# SB_MAIN.net
KiCad netlist of a schematic drawn in Altium Designer
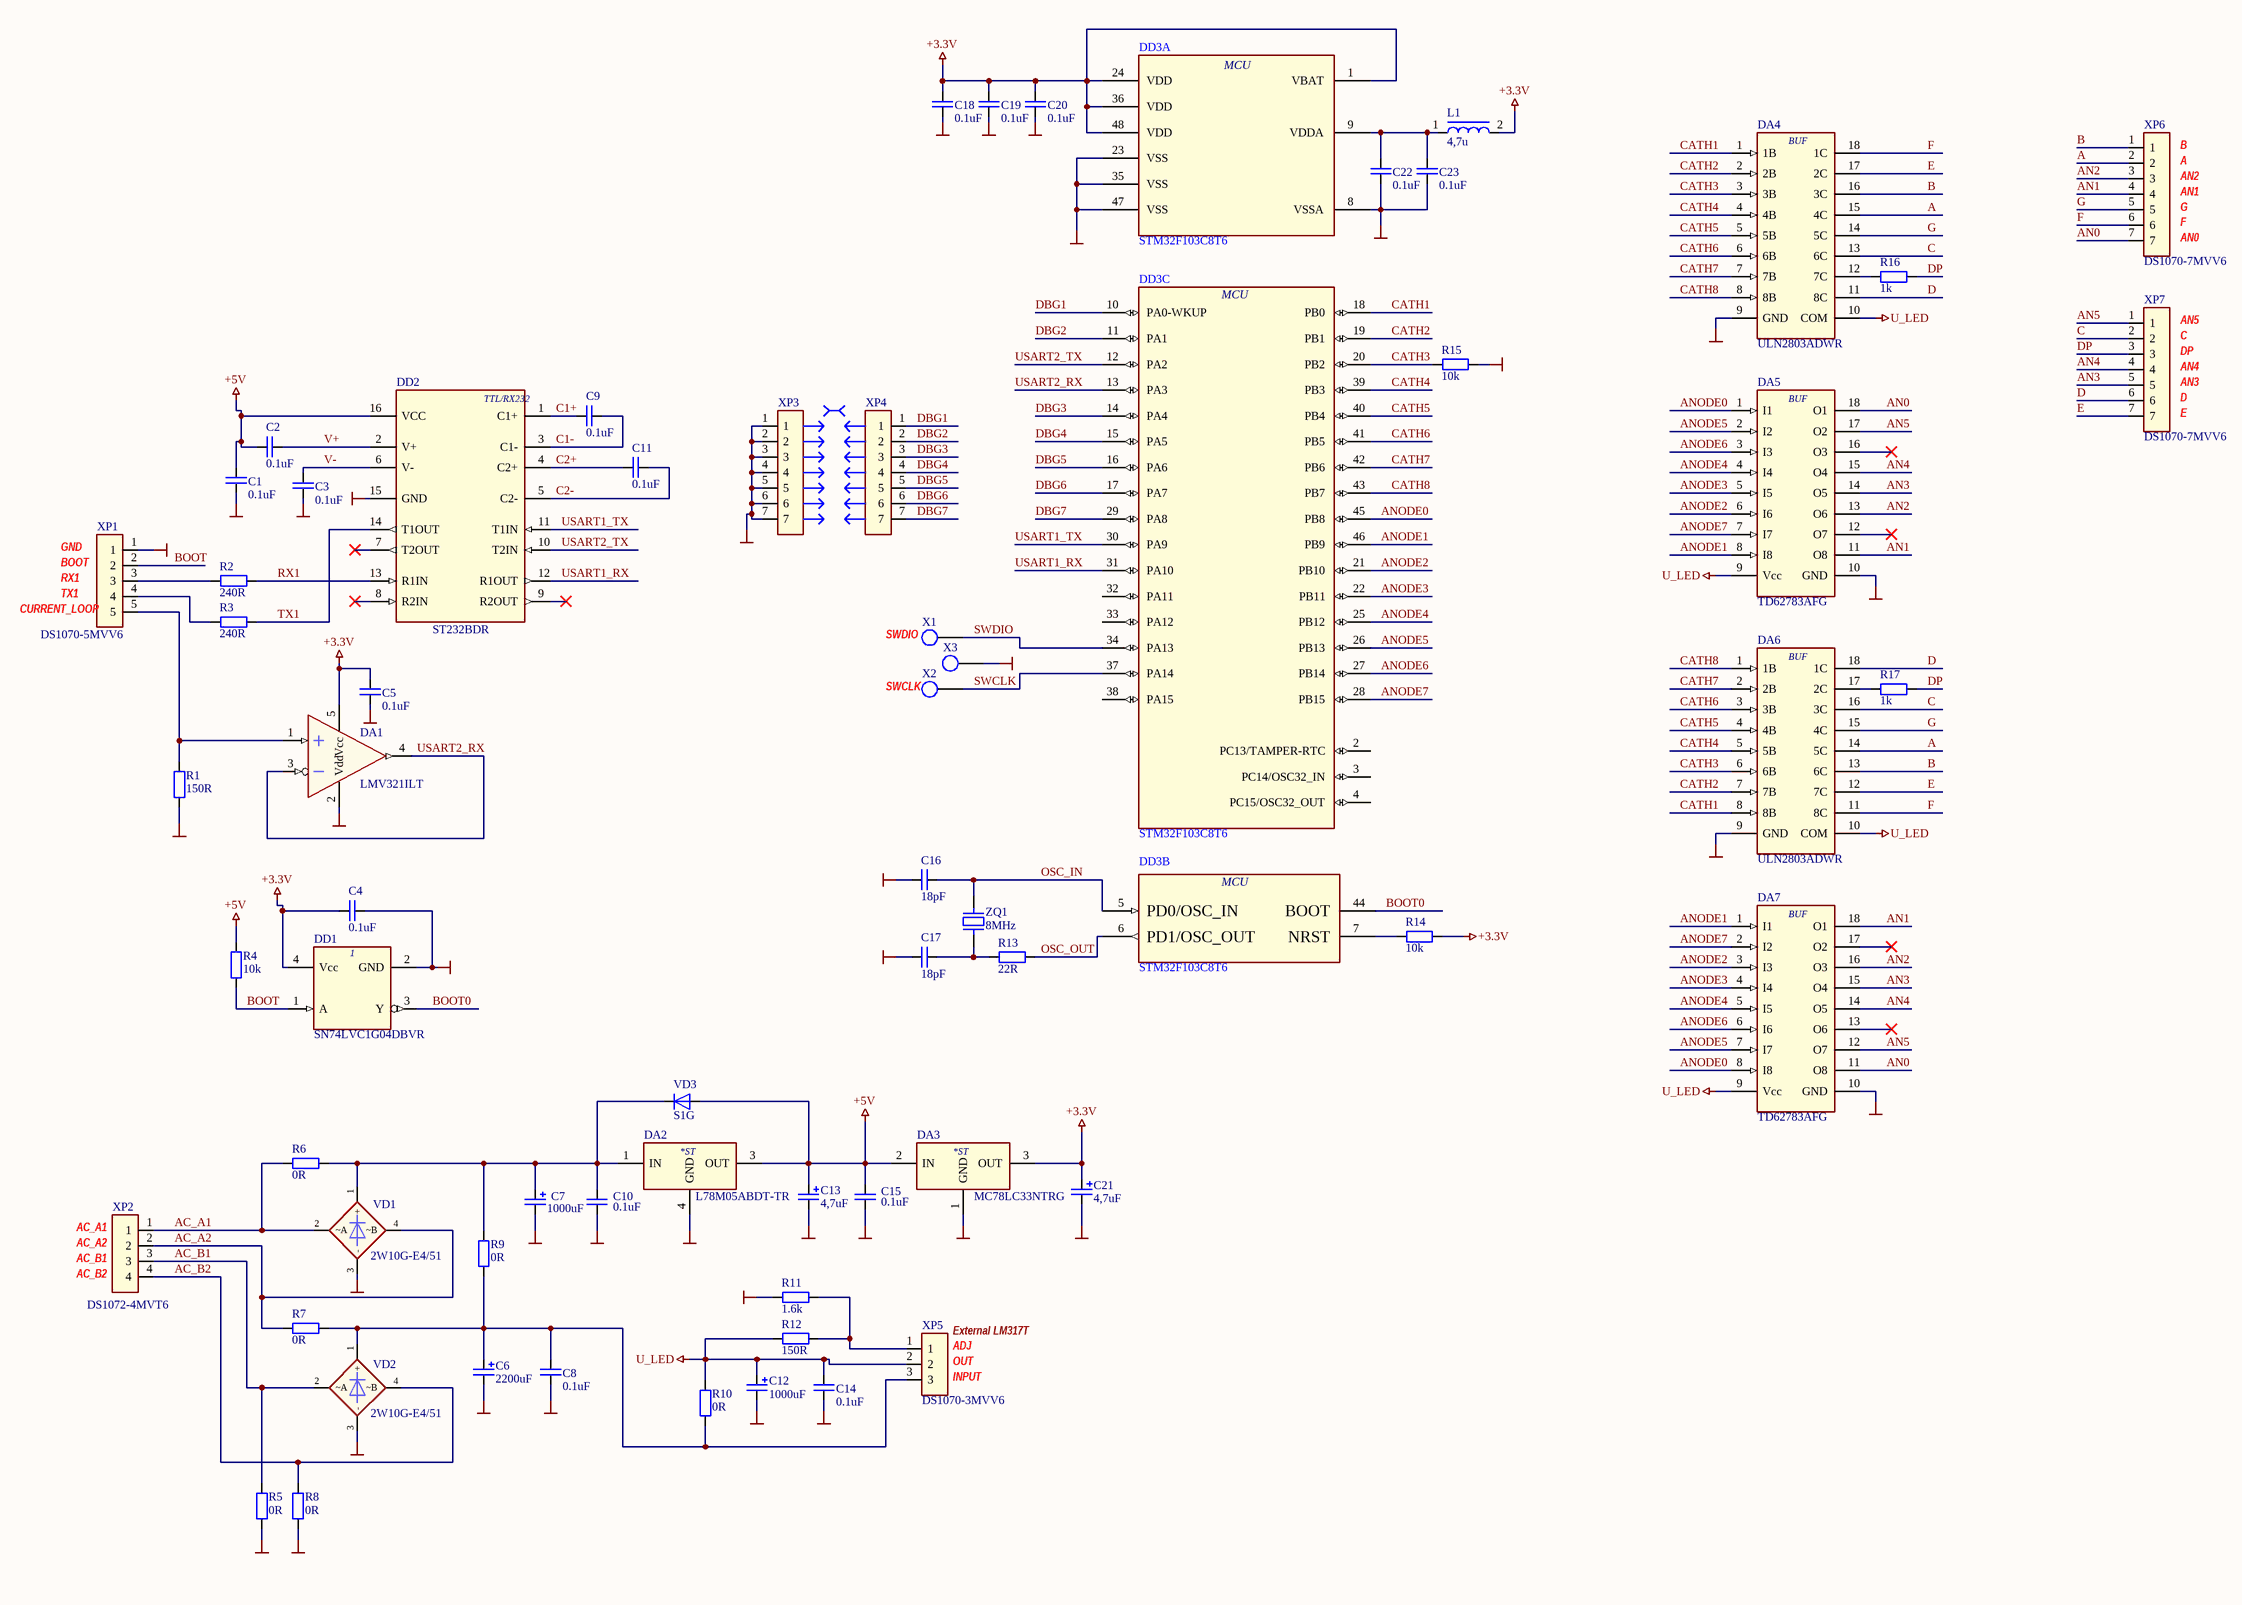
[diagram p0: SB_MAIN.SchDoc]

(export (version "E")
  (design (tool "Eeschema 10.0.6"))
  (components
    (comp (ref "C1")
      (value "0.1uF")
      (footprint "CAPC2012X14N")
      (description "Конденсатор 0805-X7R-50В-0,1мкФ ± 10%")
      (fields
        (field (name "MANUFACTURER PART NUMBER") "GRM21BR71H104KA01L")
        (field (name "MANUFACTURER") "Murata Electronics")
      )
      (libsource (lib "configDatabaseAD") (part "CapacitorsUnpolarized"))
    )
    (comp (ref "C2")
      (value "0.1uF")
      (footprint "CAPC2012X14N")
      (description "Конденсатор 0805-X7R-50В-0,1мкФ ± 10%")
      (fields
        (field (name "MANUFACTURER PART NUMBER") "GRM21BR71H104KA01L")
        (field (name "MANUFACTURER") "Murata Electronics")
      )
      (libsource (lib "configDatabaseAD") (part "CapacitorsUnpolarized"))
    )
    (comp (ref "C3")
      (value "0.1uF")
      (footprint "CAPC2012X14N")
      (description "Конденсатор 0805-X7R-50В-0,1мкФ ± 10%")
      (fields
        (field (name "MANUFACTURER PART NUMBER") "GRM21BR71H104KA01L")
        (field (name "MANUFACTURER") "Murata Electronics")
      )
      (libsource (lib "configDatabaseAD") (part "CapacitorsUnpolarized"))
    )
    (comp (ref "C4")
      (value "0.1uF")
      (footprint "CAPC2012X14N")
      (description "Конденсатор 0805-X7R-50В-0,1мкФ ± 10%")
      (fields
        (field (name "MANUFACTURER PART NUMBER") "GRM21BR71H104KA01L")
        (field (name "MANUFACTURER") "Murata Electronics")
      )
      (libsource (lib "configDatabaseAD") (part "CapacitorsUnpolarized"))
    )
    (comp (ref "C5")
      (value "0.1uF")
      (footprint "CAPC2012X14N")
      (description "Конденсатор 0805-X7R-50В-0,1мкФ ± 10%")
      (fields
        (field (name "MANUFACTURER PART NUMBER") "GRM21BR71H104KA01L")
        (field (name "MANUFACTURER") "Murata Electronics")
      )
      (libsource (lib "configDatabaseAD") (part "CapacitorsUnpolarized"))
    )
    (comp (ref "C6")
      (value "2200uF")
      (footprint "CAPR16X25")
      (description "Конденсатор электролитический 35В-2200мкФ ± 20%")
      (fields
        (field (name "MANUFACTURER PART NUMBER") "TKR222M1VK25")
        (field (name "MANUFACTURER") "Jamicon")
      )
      (libsource (lib "configDatabaseAD") (part "CapacitorsPolarized"))
    )
    (comp (ref "C7")
      (value "1000uF")
      (footprint "CAPR10x21")
      (description "Конденсатор электролитический 25В-1000мкФ ± 20%")
      (fields
        (field (name "MANUFACTURER PART NUMBER") "WLR102M1EG21")
        (field (name "MANUFACTURER") "Jamicon")
      )
      (libsource (lib "configDatabaseAD") (part "CapacitorsPolarized"))
    )
    (comp (ref "C8")
      (value "0.1uF")
      (footprint "JFA11x13x7.5")
      (description "Конденсатор-100В-0,1мкФ ± 5%")
      (fields
        (field (name "MANUFACTURER PART NUMBER") "JFA02A104J075000B")
        (field (name "MANUFACTURER") "JB")
      )
      (libsource (lib "configDatabaseAD") (part "CapacitorsUnpolarized"))
    )
    (comp (ref "C9")
      (value "0.1uF")
      (footprint "CAPC2012X14N")
      (description "Конденсатор 0805-X7R-50В-0,1мкФ ± 10%")
      (fields
        (field (name "MANUFACTURER PART NUMBER") "GRM21BR71H104KA01L")
        (field (name "MANUFACTURER") "Murata Electronics")
      )
      (libsource (lib "configDatabaseAD") (part "CapacitorsUnpolarized"))
    )
    (comp (ref "C10")
      (value "0.1uF")
      (footprint "JFA11x13x7.5")
      (description "Конденсатор-100В-0,1мкФ ± 5%")
      (fields
        (field (name "MANUFACTURER PART NUMBER") "JFA02A104J075000B")
        (field (name "MANUFACTURER") "JB")
      )
      (libsource (lib "configDatabaseAD") (part "CapacitorsUnpolarized"))
    )
    (comp (ref "C11")
      (value "0.1uF")
      (footprint "CAPC2012X14N")
      (description "Конденсатор 0805-X7R-50В-0,1мкФ ± 10%")
      (fields
        (field (name "MANUFACTURER PART NUMBER") "GRM21BR71H104KA01L")
        (field (name "MANUFACTURER") "Murata Electronics")
      )
      (libsource (lib "configDatabaseAD") (part "CapacitorsUnpolarized"))
    )
    (comp (ref "C12")
      (value "1000uF")
      (footprint "CAPR10x21")
      (description "Конденсатор электролитический 25В-1000мкФ ± 20%")
      (fields
        (field (name "MANUFACTURER PART NUMBER") "WLR102M1EG21")
        (field (name "MANUFACTURER") "Jamicon")
      )
      (libsource (lib "configDatabaseAD") (part "CapacitorsPolarized"))
    )
    (comp (ref "C13")
      (value "4,7uF")
      (footprint "CAPMP3217X18N")
      (description "Конденсатор танталовый 10В-4,7мкФ ± 10%")
      (fields
        (field (name "MANUFACTURER PART NUMBER") "TECAP4,7/10VA10")
        (field (name "MANUFACTURER") "NoName")
      )
      (libsource (lib "configDatabaseAD") (part "CapacitorsPolarized"))
    )
    (comp (ref "C14")
      (value "0.1uF")
      (footprint "JFA11x13x7.5")
      (description "Конденсатор-100В-0,1мкФ ± 5%")
      (fields
        (field (name "MANUFACTURER PART NUMBER") "JFA02A104J075000B")
        (field (name "MANUFACTURER") "JB")
      )
      (libsource (lib "configDatabaseAD") (part "CapacitorsUnpolarized"))
    )
    (comp (ref "C15")
      (value "0.1uF")
      (footprint "JFA11x13x7.5")
      (description "Конденсатор-100В-0,1мкФ ± 5%")
      (fields
        (field (name "MANUFACTURER PART NUMBER") "JFA02A104J075000B")
        (field (name "MANUFACTURER") "JB")
      )
      (libsource (lib "configDatabaseAD") (part "CapacitorsUnpolarized"))
    )
    (comp (ref "C16")
      (value "18pF")
      (footprint "CAPC2012X14N")
      (description "Конденсатор 0805-C0G-50В-18пФ ± 5%")
      (fields
        (field (name "MANUFACTURER PART NUMBER") "GRM2165C1H180JD01D")
        (field (name "MANUFACTURER") "Murata Electronics")
      )
      (libsource (lib "configDatabaseAD") (part "CapacitorsUnpolarized"))
    )
    (comp (ref "C17")
      (value "18pF")
      (footprint "CAPC2012X14N")
      (description "Конденсатор 0805-C0G-50В-18пФ ± 5%")
      (fields
        (field (name "MANUFACTURER PART NUMBER") "GRM2165C1H180JD01D")
        (field (name "MANUFACTURER") "Murata Electronics")
      )
      (libsource (lib "configDatabaseAD") (part "CapacitorsUnpolarized"))
    )
    (comp (ref "C18")
      (value "0.1uF")
      (footprint "CAPC2012X14N")
      (description "Конденсатор 0805-X7R-50В-0,1мкФ ± 10%")
      (fields
        (field (name "MANUFACTURER PART NUMBER") "GRM21BR71H104KA01L")
        (field (name "MANUFACTURER") "Murata Electronics")
      )
      (libsource (lib "configDatabaseAD") (part "CapacitorsUnpolarized"))
    )
    (comp (ref "C19")
      (value "0.1uF")
      (footprint "CAPC2012X14N")
      (description "Конденсатор 0805-X7R-50В-0,1мкФ ± 10%")
      (fields
        (field (name "MANUFACTURER PART NUMBER") "GRM21BR71H104KA01L")
        (field (name "MANUFACTURER") "Murata Electronics")
      )
      (libsource (lib "configDatabaseAD") (part "CapacitorsUnpolarized"))
    )
    (comp (ref "C20")
      (value "0.1uF")
      (footprint "CAPC2012X14N")
      (description "Конденсатор 0805-X7R-50В-0,1мкФ ± 10%")
      (fields
        (field (name "MANUFACTURER PART NUMBER") "GRM21BR71H104KA01L")
        (field (name "MANUFACTURER") "Murata Electronics")
      )
      (libsource (lib "configDatabaseAD") (part "CapacitorsUnpolarized"))
    )
    (comp (ref "C21")
      (value "4,7uF")
      (footprint "CAPMP3217X18N")
      (description "Конденсатор танталовый 10В-4,7мкФ ± 10%")
      (fields
        (field (name "MANUFACTURER PART NUMBER") "TECAP4,7/10VA10")
        (field (name "MANUFACTURER") "NoName")
      )
      (libsource (lib "configDatabaseAD") (part "CapacitorsPolarized"))
    )
    (comp (ref "C22")
      (value "0.1uF")
      (footprint "CAPC2012X14N")
      (description "Конденсатор 0805-X7R-50В-0,1мкФ ± 10%")
      (fields
        (field (name "MANUFACTURER PART NUMBER") "GRM21BR71H104KA01L")
        (field (name "MANUFACTURER") "Murata Electronics")
      )
      (libsource (lib "configDatabaseAD") (part "CapacitorsUnpolarized"))
    )
    (comp (ref "C23")
      (value "0.1uF")
      (footprint "CAPC2012X14N")
      (description "Конденсатор 0805-X7R-50В-0,1мкФ ± 10%")
      (fields
        (field (name "MANUFACTURER PART NUMBER") "GRM21BR71H104KA01L")
        (field (name "MANUFACTURER") "Murata Electronics")
      )
      (libsource (lib "configDatabaseAD") (part "CapacitorsUnpolarized"))
    )
    (comp (ref "DA1")
      (value "LMV321ILT")
      (footprint "SOT95P280X145-5N")
      (description "Микросхема LMV321ILT")
      (fields (field (name "MANUFACTURER") "STMicroelectronics"))
      (libsource (lib "configDatabaseAD") (part "LMV321ILT"))
    )
    (comp (ref "DA2")
      (value "L78M05ABDT-TR")
      (footprint "DPAK228P1010X238-3N")
      (description "Микросхема L78M05ABDT-TR")
      (fields (field (name "MANUFACTURER") "STMicroelectronics"))
      (libsource (lib "configDatabaseAD") (part "L78MxxxxDT-TR"))
    )
    (comp (ref "DA3")
      (value "MC78LC33NTRG")
      (footprint "SOT89-150P350X160-3M")
      (description "Микросхема MC78LC33NTRG")
      (fields (field (name "MANUFACTURER") "ON Semiconductor"))
      (libsource (lib "configDatabaseAD") (part "MC78LCxxNTRG"))
    )
    (comp (ref "DA4")
      (value "ULN2803ADWR")
      (footprint "SOIC127P1030X265-18N")
      (description "Микросхема ULN2803ADWR")
      (fields (field (name "MANUFACTURER") "Texas Instruments"))
      (libsource (lib "configDatabaseAD") (part "ULN2803A"))
    )
    (comp (ref "DA5")
      (value "TD62783AFG")
      (footprint "SOIC127P1020X245-18N")
      (description "Микросхема TD62783AFG")
      (fields (field (name "MANUFACTURER") "Toshiba"))
      (libsource (lib "configDatabaseAD") (part "TD62783"))
    )
    (comp (ref "DA6")
      (value "ULN2803ADWR")
      (footprint "SOIC127P1030X265-18N")
      (description "Микросхема ULN2803ADWR")
      (fields (field (name "MANUFACTURER") "Texas Instruments"))
      (libsource (lib "configDatabaseAD") (part "ULN2803A"))
    )
    (comp (ref "DA7")
      (value "TD62783AFG")
      (footprint "SOIC127P1020X245-18N")
      (description "Микросхема TD62783AFG")
      (fields (field (name "MANUFACTURER") "Toshiba"))
      (libsource (lib "configDatabaseAD") (part "TD62783"))
    )
    (comp (ref "DD1")
      (value "SN74LVC1G04DBVR")
      (footprint "SOT95P280X145-5N")
      (description "Микросхема SN74LVC1G04DBVR")
      (fields (field (name "MANUFACTURER") "Texas Instruments"))
      (libsource (lib "configDatabaseAD") (part "SN74LVC1G04"))
    )
    (comp (ref "DD2")
      (value "ST232BDR")
      (footprint "SOIC127P600X175-16N")
      (description "Микросхема ST232BDR")
      (fields (field (name "MANUFACTURER") "STMicroelectronics"))
      (libsource (lib "configDatabaseAD") (part "ST232"))
    )
    (comp (ref "DD3")
      (value "STM32F103C8T6")
      (footprint "TSQFP50P900X900X160-48M")
      (description "Микросхема STM32F103C8T6")
      (fields (field (name "MANUFACTURER") "STMicroelectronics"))
      (libsource (lib "configDatabaseAD") (part "STM32F103Cxxx"))
    )
    (comp (ref "L1")
      (value "4,7u")
      (footprint "INDC2012X10N")
      (description "Индуктивность 0805-4,7мкГ ± 30%")
      (fields
        (field (name "MANUFACTURER PART NUMBER") "LQM21PN4R7NGR")
        (field (name "MANUFACTURER") "Murata Electronics")
      )
      (libsource (lib "configDatabaseAD") (part "Inductor"))
    )
    (comp (ref "R1")
      (value "150R")
      (footprint "RESC2012X06N")
      (description "Резистор 0805-0,125Вт-150Ом ± 1%")
      (fields
        (field (name "MANUFACTURER PART NUMBER") "RC0805FR-07150RL")
        (field (name "MANUFACTURER") "Yageo")
      )
      (libsource (lib "configDatabaseAD") (part "Resistor"))
    )
    (comp (ref "R2")
      (value "240R")
      (footprint "RESC2012X06N")
      (description "Резистор 0805-0,125Вт-240Ом ± 1%")
      (fields
        (field (name "MANUFACTURER PART NUMBER") "RC0805FR-07240RL")
        (field (name "MANUFACTURER") "Yageo")
      )
      (libsource (lib "configDatabaseAD") (part "Resistor"))
    )
    (comp (ref "R3")
      (value "240R")
      (footprint "RESC2012X06N")
      (description "Резистор 0805-0,125Вт-240Ом ± 1%")
      (fields
        (field (name "MANUFACTURER PART NUMBER") "RC0805FR-07240RL")
        (field (name "MANUFACTURER") "Yageo")
      )
      (libsource (lib "configDatabaseAD") (part "Resistor"))
    )
    (comp (ref "R4")
      (value "10k")
      (footprint "RESC2012X06N")
      (description "Резистор 0805-0,125Вт-10кОм ± 1%")
      (fields
        (field (name "MANUFACTURER PART NUMBER") "RC0805FR-0710KL")
        (field (name "MANUFACTURER") "Yageo")
      )
      (libsource (lib "configDatabaseAD") (part "Resistor"))
    )
    (comp (ref "R5")
      (value "0R")
      (footprint "RESC6332X06N")
      (description "Резистор 2512-1Вт-0Ом ± 1%")
      (fields
        (field (name "MANUFACTURER PART NUMBER") "RC2512FR-070RL")
        (field (name "MANUFACTURER") "Yageo")
      )
      (libsource (lib "configDatabaseAD") (part "Resistor"))
    )
    (comp (ref "R6")
      (value "0R")
      (footprint "RESC6332X06N")
      (description "Резистор 2512-1Вт-0Ом ± 1%")
      (fields
        (field (name "MANUFACTURER PART NUMBER") "RC2512FR-070RL")
        (field (name "MANUFACTURER") "Yageo")
      )
      (libsource (lib "configDatabaseAD") (part "Resistor"))
    )
    (comp (ref "R7")
      (value "0R")
      (footprint "RESC6332X06N")
      (description "Резистор 2512-1Вт-0Ом ± 1%")
      (fields
        (field (name "MANUFACTURER PART NUMBER") "RC2512FR-070RL")
        (field (name "MANUFACTURER") "Yageo")
      )
      (libsource (lib "configDatabaseAD") (part "Resistor"))
    )
    (comp (ref "R8")
      (value "0R")
      (footprint "RESC6332X06N")
      (description "Резистор 2512-1Вт-0Ом ± 1%")
      (fields
        (field (name "MANUFACTURER PART NUMBER") "RC2512FR-070RL")
        (field (name "MANUFACTURER") "Yageo")
      )
      (libsource (lib "configDatabaseAD") (part "Resistor"))
    )
    (comp (ref "R9")
      (value "0R")
      (footprint "RESC6332X06N")
      (description "Резистор 2512-1Вт-0Ом ± 1%")
      (fields
        (field (name "MANUFACTURER PART NUMBER") "RC2512FR-070RL")
        (field (name "MANUFACTURER") "Yageo")
      )
      (libsource (lib "configDatabaseAD") (part "Resistor"))
    )
    (comp (ref "R10")
      (value "0R")
      (footprint "RESC6332X06N")
      (description "Резистор 2512-1Вт-0Ом ± 1%")
      (fields
        (field (name "MANUFACTURER PART NUMBER") "RC2512FR-070RL")
        (field (name "MANUFACTURER") "Yageo")
      )
      (libsource (lib "configDatabaseAD") (part "Resistor"))
    )
    (comp (ref "R11")
      (value "1.6k")
      (footprint "RESC2012X06N")
      (description "Резистор 0805-0,125Вт-1,6кОм ± 1%")
      (fields
        (field (name "MANUFACTURER PART NUMBER") "RC0805FR-071K6L")
        (field (name "MANUFACTURER") "Yageo")
      )
      (libsource (lib "configDatabaseAD") (part "Resistor"))
    )
    (comp (ref "R12")
      (value "150R")
      (footprint "RESC2012X06N")
      (description "Резистор 0805-0,125Вт-150Ом ± 1%")
      (fields
        (field (name "MANUFACTURER PART NUMBER") "RC0805FR-07150RL")
        (field (name "MANUFACTURER") "Yageo")
      )
      (libsource (lib "configDatabaseAD") (part "Resistor"))
    )
    (comp (ref "R13")
      (value "22R")
      (footprint "RESC2012X06N")
      (description "Резистор 0805-0,125Вт-22Ом ± 5%")
      (fields
        (field (name "MANUFACTURER PART NUMBER") "RC0805JR-0722RL")
        (field (name "MANUFACTURER") "Yageo")
      )
      (libsource (lib "configDatabaseAD") (part "Resistor"))
    )
    (comp (ref "R14")
      (value "10k")
      (footprint "RESC2012X06N")
      (description "Резистор 0805-0,125Вт-10кОм ± 1%")
      (fields
        (field (name "MANUFACTURER PART NUMBER") "RC0805FR-0710KL")
        (field (name "MANUFACTURER") "Yageo")
      )
      (libsource (lib "configDatabaseAD") (part "Resistor"))
    )
    (comp (ref "R15")
      (value "10k")
      (footprint "RESC2012X06N")
      (description "Резистор 0805-0,125Вт-10кОм ± 1%")
      (fields
        (field (name "MANUFACTURER PART NUMBER") "RC0805FR-0710KL")
        (field (name "MANUFACTURER") "Yageo")
      )
      (libsource (lib "configDatabaseAD") (part "Resistor"))
    )
    (comp (ref "R16")
      (value "1k")
      (footprint "RESC2012X06N")
      (description "Резистор 1206-0,25Вт-1кОм ± 1%")
      (fields
        (field (name "MANUFACTURER PART NUMBER") "RC1206FR-071KL")
        (field (name "MANUFACTURER") "Yageo")
      )
      (libsource (lib "configDatabaseAD") (part "Resistor"))
    )
    (comp (ref "R17")
      (value "1k")
      (footprint "RESC2012X06N")
      (description "Резистор 1206-0,25Вт-1кОм ± 1%")
      (fields
        (field (name "MANUFACTURER PART NUMBER") "RC1206FR-071KL")
        (field (name "MANUFACTURER") "Yageo")
      )
      (libsource (lib "configDatabaseAD") (part "Resistor"))
    )
    (comp (ref "VD1")
      (value "2W10G-E4/51")
      (footprint "DIOB_2W10")
      (description "Диод 2W10G-E4/51")
      (fields (field (name "MANUFACTURER") "Vishay"))
      (libsource (lib "configDatabaseAD") (part "Diod_Bridge"))
    )
    (comp (ref "VD2")
      (value "2W10G-E4/51")
      (footprint "DIOB_2W10")
      (description "Диод 2W10G-E4/51")
      (fields (field (name "MANUFACTURER") "Vishay"))
      (libsource (lib "configDatabaseAD") (part "Diod_Bridge"))
    )
    (comp (ref "VD3")
      (value "S1G")
      (footprint "DIOM4427X22M")
      (description "Диод S1G")
      (fields (field (name "MANUFACTURER") "Diotec Semiconductor"))
      (libsource (lib "configDatabaseAD") (part "Diod"))
    )
    (comp (ref "X1")
      (value "0,9mm")
      (footprint "PAD_HOLE_0.9MM")
      (fields
        (field (name "MANUFACTURER PART NUMBER") "PAD_1.8_HOLE_0.9MM")
        (field (name "MANUFACTURER") "NO BOM")
      )
      (libsource (lib "configDatabaseAD") (part "PAD_1_PIN"))
    )
    (comp (ref "X2")
      (value "0,9mm")
      (footprint "PAD_HOLE_0.9MM")
      (fields
        (field (name "MANUFACTURER PART NUMBER") "PAD_1.8_HOLE_0.9MM")
        (field (name "MANUFACTURER") "NO BOM")
      )
      (libsource (lib "configDatabaseAD") (part "PAD_1_PIN"))
    )
    (comp (ref "X3")
      (value "0,9mm")
      (footprint "PAD_HOLE_0.9MM")
      (fields
        (field (name "MANUFACTURER PART NUMBER") "PAD_1.8_HOLE_0.9MM")
        (field (name "MANUFACTURER") "NO BOM")
      )
      (libsource (lib "configDatabaseAD") (part "PAD_1_PIN"))
    )
    (comp (ref "XP1")
      (value "DS1070-5MVV6")
      (footprint "CONNFLY_DS1070-5MVV6")
      (description "Соединитель DS1070-5MVV6")
      (fields (field (name "MANUFACTURER") "Connfly"))
      (libsource (lib "configDatabaseAD") (part "Connector XP 5x1"))
    )
    (comp (ref "XP2")
      (value "DS1072-4MVT6")
      (footprint "CONNFLY_DS1072-4MVT6")
      (description "Соединитель DS1072-4MVT6")
      (fields (field (name "MANUFACTURER") "Connfly"))
      (libsource (lib "configDatabaseAD") (part "Connector XP 4x1"))
    )
    (comp (ref "XP3")
      (value "L-KLS1-207-1-07-S")
      (footprint "KLS_KLS1-207-1-07-S")
      (description "Соединитель DS1072-4MVT6")
      (fields (field (name "MANUFACTURER") "KLS"))
      (libsource (lib "configDatabaseAD") (part "Connector XP 7x1"))
    )
    (comp (ref "XP4")
      (value "L-KLS1-207-1-07-S")
      (footprint "KLS_KLS1-207-1-07-S")
      (description "Соединитель DS1072-4MVT6")
      (fields (field (name "MANUFACTURER") "KLS"))
      (libsource (lib "") (part "Connector XP 7x1_1"))
    )
    (comp (ref "XP5")
      (value "DS1070-3MVV6")
      (footprint "CONNFLY_DS1070-3MVV6")
      (description "Соединитель DS1070-3MVV6")
      (fields (field (name "MANUFACTURER") "Connfly"))
      (libsource (lib "configDatabaseAD") (part "Connector XP 3x1"))
    )
    (comp (ref "XP6")
      (value "DS1070-7MVV6")
      (footprint "CONNFLY_DS1070-7MVV6")
      (description "Соединитель DS1070-7MVV6")
      (fields (field (name "MANUFACTURER") "Connfly"))
      (libsource (lib "configDatabaseAD") (part "Connector XP 7x1"))
    )
    (comp (ref "XP7")
      (value "DS1070-7MVV6")
      (footprint "CONNFLY_DS1070-7MVV6")
      (description "Соединитель DS1070-7MVV6")
      (fields (field (name "MANUFACTURER") "Connfly"))
      (libsource (lib "configDatabaseAD") (part "Connector XP 7x1"))
    )
    (comp (ref "ZQ1")
      (value "8MHz")
      (footprint "KX-3H_spacer")
      (description "Кварцевый резонатор HC-49US-8MHz-16pF-30ppm")
      (fields
        (field (name "MANUFACTURER PART NUMBER") "HC-49US-8MHz-16pF-30ppm")
        (field (name "MANUFACTURER") "NoName")
      )
      (libsource (lib "configDatabaseAD") (part "QuartzCrystal"))
    )
  )
  (nets
    (net (code "1") (name "+3.3V") (class "Default")
      (node (ref "C18") (pin "2") (pinfunction "2_2") (pintype "passive"))
      (node (ref "C19") (pin "2") (pinfunction "2_2") (pintype "passive"))
      (node (ref "C20") (pin "2") (pinfunction "2_2") (pintype "passive"))
      (node (ref "C21") (pin "1") (pinfunction "P_1") (pintype "passive"))
      (node (ref "C4") (pin "1") (pinfunction "1_1") (pintype "passive"))
      (node (ref "C5") (pin "2") (pinfunction "2_2") (pintype "passive"))
      (node (ref "DA1") (pin "5") (pinfunction "Vcc_5") (pintype "power_in"))
      (node (ref "DA3") (pin "3") (pinfunction "OUT_3") (pintype "power_in"))
      (node (ref "DD1") (pin "4") (pinfunction "Vcc_4") (pintype "power_in"))
      (node (ref "DD3") (pin "1") (pinfunction "VBAT_1") (pintype "power_in"))
      (node (ref "DD3") (pin "24") (pinfunction "VDD_24") (pintype "power_in"))
      (node (ref "DD3") (pin "36") (pinfunction "VDD_36") (pintype "power_in"))
      (node (ref "DD3") (pin "48") (pinfunction "VDD_48") (pintype "power_in"))
      (node (ref "L1") (pin "2") (pinfunction "2_2") (pintype "passive"))
      (node (ref "R14") (pin "2") (pinfunction "2_2") (pintype "passive"))
    )
    (net (code "2") (name "+5V") (class "Default")
      (node (ref "C1") (pin "2") (pinfunction "2_2") (pintype "passive"))
      (node (ref "C13") (pin "1") (pinfunction "P_1") (pintype "passive"))
      (node (ref "C15") (pin "2") (pinfunction "2_2") (pintype "passive"))
      (node (ref "C2") (pin "1") (pinfunction "1_1") (pintype "passive"))
      (node (ref "DA2") (pin "3") (pinfunction "OUT_3") (pintype "power_in"))
      (node (ref "DA3") (pin "2") (pinfunction "IN_2") (pintype "power_in"))
      (node (ref "DD2") (pin "16") (pinfunction "VCC_16") (pintype "power_in"))
      (node (ref "R4") (pin "2") (pinfunction "2_2") (pintype "passive"))
      (node (ref "VD3") (pin "2") (pinfunction "A_2") (pintype "passive"))
    )
    (net (code "3") (name "/A") (class "Default")
      (node (ref "DA4") (pin "15") (pinfunction "4C_15") (pintype "open_collector"))
      (node (ref "DA6") (pin "14") (pinfunction "5C_14") (pintype "open_collector"))
      (node (ref "XP6") (pin "2") (pinfunction "2_2") (pintype "passive"))
    )
    (net (code "4") (name "/AC_A1") (class "Default")
      (node (ref "R6") (pin "1") (pinfunction "1_1") (pintype "passive"))
      (node (ref "VD1") (pin "2") (pinfunction "~A_2") (pintype "passive"))
      (node (ref "XP2") (pin "1") (pinfunction "1_1") (pintype "passive"))
    )
    (net (code "5") (name "/AC_A2") (class "Default")
      (node (ref "R7") (pin "1") (pinfunction "1_1") (pintype "passive"))
      (node (ref "VD1") (pin "4") (pinfunction "~B_4") (pintype "passive"))
      (node (ref "XP2") (pin "2") (pinfunction "2_2") (pintype "passive"))
    )
    (net (code "6") (name "/AC_B1") (class "Default")
      (node (ref "R5") (pin "2") (pinfunction "2_2") (pintype "passive"))
      (node (ref "VD2") (pin "2") (pinfunction "~A_2") (pintype "passive"))
      (node (ref "XP2") (pin "3") (pinfunction "3_3") (pintype "passive"))
    )
    (net (code "7") (name "/AC_B2") (class "Default")
      (node (ref "R8") (pin "2") (pinfunction "2_2") (pintype "passive"))
      (node (ref "VD2") (pin "4") (pinfunction "~B_4") (pintype "passive"))
      (node (ref "XP2") (pin "4") (pinfunction "4_4") (pintype "passive"))
    )
    (net (code "8") (name "/AN0") (class "Default")
      (node (ref "DA5") (pin "18") (pinfunction "O1_18") (pintype "open_emitter"))
      (node (ref "DA7") (pin "11") (pinfunction "O8_11") (pintype "open_emitter"))
      (node (ref "XP6") (pin "7") (pinfunction "7_7") (pintype "passive"))
    )
    (net (code "9") (name "/AN1") (class "Default")
      (node (ref "DA5") (pin "11") (pinfunction "O8_11") (pintype "open_emitter"))
      (node (ref "DA7") (pin "18") (pinfunction "O1_18") (pintype "open_emitter"))
      (node (ref "XP6") (pin "4") (pinfunction "4_4") (pintype "passive"))
    )
    (net (code "10") (name "/AN2") (class "Default")
      (node (ref "DA5") (pin "13") (pinfunction "O6_13") (pintype "open_emitter"))
      (node (ref "DA7") (pin "16") (pinfunction "O3_16") (pintype "open_emitter"))
      (node (ref "XP6") (pin "3") (pinfunction "3_3") (pintype "passive"))
    )
    (net (code "11") (name "/AN3") (class "Default")
      (node (ref "DA5") (pin "14") (pinfunction "O5_14") (pintype "open_emitter"))
      (node (ref "DA7") (pin "15") (pinfunction "O4_15") (pintype "open_emitter"))
      (node (ref "XP7") (pin "5") (pinfunction "5_5") (pintype "passive"))
    )
    (net (code "12") (name "/AN4") (class "Default")
      (node (ref "DA5") (pin "15") (pinfunction "O4_15") (pintype "open_emitter"))
      (node (ref "DA7") (pin "14") (pinfunction "O5_14") (pintype "open_emitter"))
      (node (ref "XP7") (pin "4") (pinfunction "4_4") (pintype "passive"))
    )
    (net (code "13") (name "/AN5") (class "Default")
      (node (ref "DA5") (pin "17") (pinfunction "O2_17") (pintype "open_emitter"))
      (node (ref "DA7") (pin "12") (pinfunction "O7_12") (pintype "open_emitter"))
      (node (ref "XP7") (pin "1") (pinfunction "1_1") (pintype "passive"))
    )
    (net (code "14") (name "/ANODE0") (class "Default")
      (node (ref "DA5") (pin "1") (pinfunction "I1_1") (pintype "input"))
      (node (ref "DA7") (pin "8") (pinfunction "I8_8") (pintype "input"))
      (node (ref "DD3") (pin "45") (pinfunction "PB8_45") (pintype "bidirectional"))
    )
    (net (code "15") (name "/ANODE1") (class "Default")
      (node (ref "DA5") (pin "8") (pinfunction "I8_8") (pintype "input"))
      (node (ref "DA7") (pin "1") (pinfunction "I1_1") (pintype "input"))
      (node (ref "DD3") (pin "46") (pinfunction "PB9_46") (pintype "bidirectional"))
    )
    (net (code "16") (name "/ANODE2") (class "Default")
      (node (ref "DA5") (pin "6") (pinfunction "I6_6") (pintype "input"))
      (node (ref "DA7") (pin "3") (pinfunction "I3_3") (pintype "input"))
      (node (ref "DD3") (pin "21") (pinfunction "PB10_21") (pintype "bidirectional"))
    )
    (net (code "17") (name "/ANODE3") (class "Default")
      (node (ref "DA5") (pin "5") (pinfunction "I5_5") (pintype "input"))
      (node (ref "DA7") (pin "4") (pinfunction "I4_4") (pintype "input"))
      (node (ref "DD3") (pin "22") (pinfunction "PB11_22") (pintype "bidirectional"))
    )
    (net (code "18") (name "/ANODE4") (class "Default")
      (node (ref "DA5") (pin "4") (pinfunction "I4_4") (pintype "input"))
      (node (ref "DA7") (pin "5") (pinfunction "I5_5") (pintype "input"))
      (node (ref "DD3") (pin "25") (pinfunction "PB12_25") (pintype "bidirectional"))
    )
    (net (code "19") (name "/ANODE5") (class "Default")
      (node (ref "DA5") (pin "2") (pinfunction "I2_2") (pintype "input"))
      (node (ref "DA7") (pin "7") (pinfunction "I7_7") (pintype "input"))
      (node (ref "DD3") (pin "26") (pinfunction "PB13_26") (pintype "bidirectional"))
    )
    (net (code "20") (name "/ANODE6") (class "Default")
      (node (ref "DA5") (pin "3") (pinfunction "I3_3") (pintype "input"))
      (node (ref "DA7") (pin "6") (pinfunction "I6_6") (pintype "input"))
      (node (ref "DD3") (pin "27") (pinfunction "PB14_27") (pintype "bidirectional"))
    )
    (net (code "21") (name "/ANODE7") (class "Default")
      (node (ref "DA5") (pin "7") (pinfunction "I7_7") (pintype "input"))
      (node (ref "DA7") (pin "2") (pinfunction "I2_2") (pintype "input"))
      (node (ref "DD3") (pin "28") (pinfunction "PB15_28") (pintype "bidirectional"))
    )
    (net (code "22") (name "/B") (class "Default")
      (node (ref "DA4") (pin "16") (pinfunction "3C_16") (pintype "open_collector"))
      (node (ref "DA6") (pin "13") (pinfunction "6C_13") (pintype "open_collector"))
      (node (ref "XP6") (pin "1") (pinfunction "1_1") (pintype "passive"))
    )
    (net (code "23") (name "/BOOT") (class "Default")
      (node (ref "DD1") (pin "1") (pinfunction "A_1") (pintype "input"))
      (node (ref "R4") (pin "1") (pinfunction "1_1") (pintype "passive"))
      (node (ref "XP1") (pin "2") (pinfunction "2_2") (pintype "passive"))
    )
    (net (code "24") (name "/BOOT0") (class "Default")
      (node (ref "DD1") (pin "3") (pinfunction "Y_3") (pintype "output"))
      (node (ref "DD3") (pin "44") (pinfunction "BOOT_44") (pintype "passive"))
    )
    (net (code "25") (name "/C") (class "Default")
      (node (ref "DA4") (pin "13") (pinfunction "6C_13") (pintype "open_collector"))
      (node (ref "DA6") (pin "16") (pinfunction "3C_16") (pintype "open_collector"))
      (node (ref "XP7") (pin "2") (pinfunction "2_2") (pintype "passive"))
    )
    (net (code "26") (name "/C1+") (class "Default")
      (node (ref "C9") (pin "2") (pinfunction "2_2") (pintype "passive"))
      (node (ref "DD2") (pin "1") (pinfunction "C1+_1") (pintype "passive"))
    )
    (net (code "27") (name "/C1-") (class "Default")
      (node (ref "C9") (pin "1") (pinfunction "1_1") (pintype "passive"))
      (node (ref "DD2") (pin "3") (pinfunction "C1-_3") (pintype "passive"))
    )
    (net (code "28") (name "/C2+") (class "Default")
      (node (ref "C11") (pin "2") (pinfunction "2_2") (pintype "passive"))
      (node (ref "DD2") (pin "4") (pinfunction "C2+_4") (pintype "passive"))
    )
    (net (code "29") (name "/C2-") (class "Default")
      (node (ref "C11") (pin "1") (pinfunction "1_1") (pintype "passive"))
      (node (ref "DD2") (pin "5") (pinfunction "C2-_5") (pintype "passive"))
    )
    (net (code "30") (name "/CATH1") (class "Default")
      (node (ref "DA4") (pin "1") (pinfunction "1B_1") (pintype "input"))
      (node (ref "DA6") (pin "8") (pinfunction "8B_8") (pintype "input"))
      (node (ref "DD3") (pin "18") (pinfunction "PB0_18") (pintype "bidirectional"))
    )
    (net (code "31") (name "/CATH2") (class "Default")
      (node (ref "DA4") (pin "2") (pinfunction "2B_2") (pintype "input"))
      (node (ref "DA6") (pin "7") (pinfunction "7B_7") (pintype "input"))
      (node (ref "DD3") (pin "19") (pinfunction "PB1_19") (pintype "bidirectional"))
    )
    (net (code "32") (name "/CATH3") (class "Default")
      (node (ref "DA4") (pin "3") (pinfunction "3B_3") (pintype "input"))
      (node (ref "DA6") (pin "6") (pinfunction "6B_6") (pintype "input"))
      (node (ref "DD3") (pin "20") (pinfunction "PB2_20") (pintype "bidirectional"))
      (node (ref "R15") (pin "1") (pinfunction "1_1") (pintype "passive"))
    )
    (net (code "33") (name "/CATH4") (class "Default")
      (node (ref "DA4") (pin "4") (pinfunction "4B_4") (pintype "input"))
      (node (ref "DA6") (pin "5") (pinfunction "5B_5") (pintype "input"))
      (node (ref "DD3") (pin "39") (pinfunction "PB3_39") (pintype "bidirectional"))
    )
    (net (code "34") (name "/CATH5") (class "Default")
      (node (ref "DA4") (pin "5") (pinfunction "5B_5") (pintype "input"))
      (node (ref "DA6") (pin "4") (pinfunction "4B_4") (pintype "input"))
      (node (ref "DD3") (pin "40") (pinfunction "PB4_40") (pintype "bidirectional"))
    )
    (net (code "35") (name "/CATH6") (class "Default")
      (node (ref "DA4") (pin "6") (pinfunction "6B_6") (pintype "input"))
      (node (ref "DA6") (pin "3") (pinfunction "3B_3") (pintype "input"))
      (node (ref "DD3") (pin "41") (pinfunction "PB5_41") (pintype "bidirectional"))
    )
    (net (code "36") (name "/CATH7") (class "Default")
      (node (ref "DA4") (pin "7") (pinfunction "7B_7") (pintype "input"))
      (node (ref "DA6") (pin "2") (pinfunction "2B_2") (pintype "input"))
      (node (ref "DD3") (pin "42") (pinfunction "PB6_42") (pintype "bidirectional"))
    )
    (net (code "37") (name "/CATH8") (class "Default")
      (node (ref "DA4") (pin "8") (pinfunction "8B_8") (pintype "input"))
      (node (ref "DA6") (pin "1") (pinfunction "1B_1") (pintype "input"))
      (node (ref "DD3") (pin "43") (pinfunction "PB7_43") (pintype "bidirectional"))
    )
    (net (code "38") (name "/D") (class "Default")
      (node (ref "DA4") (pin "11") (pinfunction "8C_11") (pintype "open_collector"))
      (node (ref "DA6") (pin "18") (pinfunction "1C_18") (pintype "open_collector"))
      (node (ref "XP7") (pin "6") (pinfunction "6_6") (pintype "passive"))
    )
    (net (code "39") (name "/DBG1") (class "Default")
      (node (ref "DD3") (pin "10") (pinfunction "PA0-WKUP_10") (pintype "bidirectional"))
      (node (ref "XP4") (pin "1") (pinfunction "1_1") (pintype "passive"))
    )
    (net (code "40") (name "/DBG2") (class "Default")
      (node (ref "DD3") (pin "11") (pinfunction "PA1_11") (pintype "bidirectional"))
      (node (ref "XP4") (pin "2") (pinfunction "2_2") (pintype "passive"))
    )
    (net (code "41") (name "/DBG3") (class "Default")
      (node (ref "DD3") (pin "14") (pinfunction "PA4_14") (pintype "bidirectional"))
      (node (ref "XP4") (pin "3") (pinfunction "3_3") (pintype "passive"))
    )
    (net (code "42") (name "/DBG4") (class "Default")
      (node (ref "DD3") (pin "15") (pinfunction "PA5_15") (pintype "bidirectional"))
      (node (ref "XP4") (pin "4") (pinfunction "4_4") (pintype "passive"))
    )
    (net (code "43") (name "/DBG5") (class "Default")
      (node (ref "DD3") (pin "16") (pinfunction "PA6_16") (pintype "bidirectional"))
      (node (ref "XP4") (pin "5") (pinfunction "5_5") (pintype "passive"))
    )
    (net (code "44") (name "/DBG6") (class "Default")
      (node (ref "DD3") (pin "17") (pinfunction "PA7_17") (pintype "bidirectional"))
      (node (ref "XP4") (pin "6") (pinfunction "6_6") (pintype "passive"))
    )
    (net (code "45") (name "/DBG7") (class "Default")
      (node (ref "DD3") (pin "29") (pinfunction "PA8_29") (pintype "bidirectional"))
      (node (ref "XP4") (pin "7") (pinfunction "7_7") (pintype "passive"))
    )
    (net (code "46") (name "/DP") (class "Default")
      (node (ref "R16") (pin "2") (pinfunction "2_2") (pintype "passive"))
      (node (ref "R17") (pin "2") (pinfunction "2_2") (pintype "passive"))
      (node (ref "XP7") (pin "3") (pinfunction "3_3") (pintype "passive"))
    )
    (net (code "47") (name "/E") (class "Default")
      (node (ref "DA4") (pin "17") (pinfunction "2C_17") (pintype "open_collector"))
      (node (ref "DA6") (pin "12") (pinfunction "7C_12") (pintype "open_collector"))
      (node (ref "XP7") (pin "7") (pinfunction "7_7") (pintype "passive"))
    )
    (net (code "48") (name "/F") (class "Default")
      (node (ref "DA4") (pin "18") (pinfunction "1C_18") (pintype "open_collector"))
      (node (ref "DA6") (pin "11") (pinfunction "8C_11") (pintype "open_collector"))
      (node (ref "XP6") (pin "6") (pinfunction "6_6") (pintype "passive"))
    )
    (net (code "49") (name "/G") (class "Default")
      (node (ref "DA4") (pin "14") (pinfunction "5C_14") (pintype "open_collector"))
      (node (ref "DA6") (pin "15") (pinfunction "4C_15") (pintype "open_collector"))
      (node (ref "XP6") (pin "5") (pinfunction "5_5") (pintype "passive"))
    )
    (net (code "50") (name "/OSC_IN") (class "Default")
      (node (ref "C16") (pin "2") (pinfunction "2_2") (pintype "passive"))
      (node (ref "DD3") (pin "5") (pinfunction "PD0/OSC_IN_5") (pintype "input"))
      (node (ref "ZQ1") (pin "2") (pinfunction "2_2") (pintype "passive"))
    )
    (net (code "51") (name "/OSC_OUT") (class "Default")
      (node (ref "DD3") (pin "6") (pinfunction "PD1/OSC_OUT_6") (pintype "output"))
      (node (ref "R13") (pin "2") (pinfunction "2_2") (pintype "passive"))
    )
    (net (code "52") (name "/RX1") (class "Default")
      (node (ref "DD2") (pin "13") (pinfunction "R1IN_13") (pintype "input"))
      (node (ref "R2") (pin "2") (pinfunction "2_2") (pintype "passive"))
    )
    (net (code "53") (name "/SWCLK") (class "Default")
      (node (ref "DD3") (pin "37") (pinfunction "PA14_37") (pintype "bidirectional"))
      (node (ref "X2") (pin "1") (pinfunction "1_1") (pintype "passive"))
    )
    (net (code "54") (name "/SWDIO") (class "Default")
      (node (ref "DD3") (pin "34") (pinfunction "PA13_34") (pintype "bidirectional"))
      (node (ref "X1") (pin "1") (pinfunction "1_1") (pintype "passive"))
    )
    (net (code "55") (name "/TX1") (class "Default")
      (node (ref "DD2") (pin "14") (pinfunction "T1OUT_14") (pintype "output"))
      (node (ref "R3") (pin "2") (pinfunction "2_2") (pintype "passive"))
    )
    (net (code "56") (name "/USART1_RX") (class "Default")
      (node (ref "DD2") (pin "12") (pinfunction "R1OUT_12") (pintype "output"))
      (node (ref "DD3") (pin "31") (pinfunction "PA10_31") (pintype "bidirectional"))
    )
    (net (code "57") (name "/USART1_TX") (class "Default")
      (node (ref "DD2") (pin "11") (pinfunction "T1IN_11") (pintype "input"))
      (node (ref "DD3") (pin "30") (pinfunction "PA9_30") (pintype "bidirectional"))
    )
    (net (code "58") (name "/USART2_RX") (class "Default")
      (node (ref "DA1") (pin "3") (pinfunction "-IN_3") (pintype "input"))
      (node (ref "DA1") (pin "4") (pinfunction "OUT_4") (pintype "output"))
      (node (ref "DD3") (pin "13") (pinfunction "PA3_13") (pintype "bidirectional"))
    )
    (net (code "59") (name "/USART2_TX") (class "Default")
      (node (ref "DD2") (pin "10") (pinfunction "T2IN_10") (pintype "input"))
      (node (ref "DD3") (pin "12") (pinfunction "PA2_12") (pintype "bidirectional"))
    )
    (net (code "60") (name "/V+") (class "Default")
      (node (ref "C2") (pin "2") (pinfunction "2_2") (pintype "passive"))
      (node (ref "DD2") (pin "2") (pinfunction "V+_2") (pintype "passive"))
    )
    (net (code "61") (name "/V-") (class "Default")
      (node (ref "C3") (pin "1") (pinfunction "1_1") (pintype "passive"))
      (node (ref "DD2") (pin "6") (pinfunction "V-_6") (pintype "passive"))
    )
    (net (code "62") (name "GND") (class "Default")
      (node (ref "C1") (pin "1") (pinfunction "1_1") (pintype "passive"))
      (node (ref "C10") (pin "1") (pinfunction "1_1") (pintype "passive"))
      (node (ref "C12") (pin "2") (pinfunction "N_2") (pintype "passive"))
      (node (ref "C13") (pin "2") (pinfunction "N_2") (pintype "passive"))
      (node (ref "C14") (pin "1") (pinfunction "1_1") (pintype "passive"))
      (node (ref "C15") (pin "1") (pinfunction "1_1") (pintype "passive"))
      (node (ref "C16") (pin "1") (pinfunction "1_1") (pintype "passive"))
      (node (ref "C17") (pin "1") (pinfunction "1_1") (pintype "passive"))
      (node (ref "C18") (pin "1") (pinfunction "1_1") (pintype "passive"))
      (node (ref "C19") (pin "1") (pinfunction "1_1") (pintype "passive"))
      (node (ref "C20") (pin "1") (pinfunction "1_1") (pintype "passive"))
      (node (ref "C21") (pin "2") (pinfunction "N_2") (pintype "passive"))
      (node (ref "C22") (pin "1") (pinfunction "1_1") (pintype "passive"))
      (node (ref "C23") (pin "1") (pinfunction "1_1") (pintype "passive"))
      (node (ref "C3") (pin "2") (pinfunction "2_2") (pintype "passive"))
      (node (ref "C4") (pin "2") (pinfunction "2_2") (pintype "passive"))
      (node (ref "C5") (pin "1") (pinfunction "1_1") (pintype "passive"))
      (node (ref "C6") (pin "2") (pinfunction "N_2") (pintype "passive"))
      (node (ref "C7") (pin "2") (pinfunction "N_2") (pintype "passive"))
      (node (ref "C8") (pin "1") (pinfunction "1_1") (pintype "passive"))
      (node (ref "DA1") (pin "2") (pinfunction "Vdd_2") (pintype "power_in"))
      (node (ref "DA2") (pin "4") (pinfunction "GND_4") (pintype "power_in"))
      (node (ref "DA3") (pin "1") (pinfunction "GND_1") (pintype "power_in"))
      (node (ref "DA4") (pin "9") (pinfunction "GND_9") (pintype "power_in"))
      (node (ref "DA5") (pin "10") (pinfunction "GND_10") (pintype "power_in"))
      (node (ref "DA6") (pin "9") (pinfunction "GND_9") (pintype "power_in"))
      (node (ref "DA7") (pin "10") (pinfunction "GND_10") (pintype "power_in"))
      (node (ref "DD1") (pin "2") (pinfunction "GND_2") (pintype "power_in"))
      (node (ref "DD2") (pin "15") (pinfunction "GND_15") (pintype "power_in"))
      (node (ref "DD3") (pin "23") (pinfunction "VSS_23") (pintype "power_in"))
      (node (ref "DD3") (pin "35") (pinfunction "VSS_35") (pintype "power_in"))
      (node (ref "DD3") (pin "47") (pinfunction "VSS_47") (pintype "power_in"))
      (node (ref "DD3") (pin "8") (pinfunction "VSSA_8") (pintype "power_in"))
      (node (ref "R1") (pin "1") (pinfunction "1_1") (pintype "passive"))
      (node (ref "R11") (pin "1") (pinfunction "1_1") (pintype "passive"))
      (node (ref "R15") (pin "2") (pinfunction "2_2") (pintype "passive"))
      (node (ref "R5") (pin "1") (pinfunction "1_1") (pintype "passive"))
      (node (ref "R8") (pin "1") (pinfunction "1_1") (pintype "passive"))
      (node (ref "VD1") (pin "3") (pinfunction "-_3") (pintype "passive"))
      (node (ref "VD2") (pin "3") (pinfunction "-_3") (pintype "passive"))
      (node (ref "X3") (pin "1") (pinfunction "1_1") (pintype "passive"))
      (node (ref "XP1") (pin "1") (pinfunction "1_1") (pintype "passive"))
      (node (ref "XP3") (pin "1") (pinfunction "1_1") (pintype "passive"))
      (node (ref "XP3") (pin "2") (pinfunction "2_2") (pintype "passive"))
      (node (ref "XP3") (pin "3") (pinfunction "3_3") (pintype "passive"))
      (node (ref "XP3") (pin "4") (pinfunction "4_4") (pintype "passive"))
      (node (ref "XP3") (pin "5") (pinfunction "5_5") (pintype "passive"))
      (node (ref "XP3") (pin "6") (pinfunction "6_6") (pintype "passive"))
      (node (ref "XP3") (pin "7") (pinfunction "7_7") (pintype "passive"))
    )
    (net (code "63") (name "Net-(C6-P)") (class "Default")
      (node (ref "C6") (pin "1") (pinfunction "P_1") (pintype "passive"))
      (node (ref "C8") (pin "2") (pinfunction "2_2") (pintype "passive"))
      (node (ref "R10") (pin "1") (pinfunction "1_1") (pintype "passive"))
      (node (ref "R7") (pin "2") (pinfunction "2_2") (pintype "passive"))
      (node (ref "R9") (pin "1") (pinfunction "1_1") (pintype "passive"))
      (node (ref "VD2") (pin "1") (pinfunction "+_1") (pintype "passive"))
      (node (ref "XP5") (pin "3") (pinfunction "3_3") (pintype "passive"))
    )
    (net (code "64") (name "Net-(C7-P)") (class "Default")
      (node (ref "C10") (pin "2") (pinfunction "2_2") (pintype "passive"))
      (node (ref "C7") (pin "1") (pinfunction "P_1") (pintype "passive"))
      (node (ref "DA2") (pin "1") (pinfunction "IN_1") (pintype "power_in"))
      (node (ref "R6") (pin "2") (pinfunction "2_2") (pintype "passive"))
      (node (ref "R9") (pin "2") (pinfunction "2_2") (pintype "passive"))
      (node (ref "VD1") (pin "1") (pinfunction "+_1") (pintype "passive"))
      (node (ref "VD3") (pin "1") (pinfunction "K_1") (pintype "passive"))
    )
    (net (code "65") (name "Net-(C17-Pad2)") (class "Default")
      (node (ref "C17") (pin "2") (pinfunction "2_2") (pintype "passive"))
      (node (ref "R13") (pin "1") (pinfunction "1_1") (pintype "passive"))
      (node (ref "ZQ1") (pin "1") (pinfunction "1_1") (pintype "passive"))
    )
    (net (code "66") (name "Net-(DA1-+IN)") (class "Default")
      (node (ref "DA1") (pin "1") (pinfunction "+IN_1") (pintype "input"))
      (node (ref "R1") (pin "2") (pinfunction "2_2") (pintype "passive"))
      (node (ref "XP1") (pin "5") (pinfunction "5_5") (pintype "passive"))
    )
    (net (code "67") (name "Net-(DA4-7C)") (class "Default")
      (node (ref "DA4") (pin "12") (pinfunction "7C_12") (pintype "open_collector"))
      (node (ref "R16") (pin "1") (pinfunction "1_1") (pintype "passive"))
    )
    (net (code "68") (name "Net-(DA6-2C)") (class "Default")
      (node (ref "DA6") (pin "17") (pinfunction "2C_17") (pintype "open_collector"))
      (node (ref "R17") (pin "1") (pinfunction "1_1") (pintype "passive"))
    )
    (net (code "69") (name "Net-(DD3A-VDDA)") (class "Default")
      (node (ref "C22") (pin "2") (pinfunction "2_2") (pintype "passive"))
      (node (ref "C23") (pin "2") (pinfunction "2_2") (pintype "passive"))
      (node (ref "DD3") (pin "9") (pinfunction "VDDA_9") (pintype "power_in"))
      (node (ref "L1") (pin "1") (pinfunction "1_1") (pintype "passive"))
    )
    (net (code "70") (name "Net-(DD3B-NRST)") (class "Default")
      (node (ref "DD3") (pin "7") (pinfunction "NRST_7") (pintype "passive"))
      (node (ref "R14") (pin "1") (pinfunction "1_1") (pintype "passive"))
    )
    (net (code "71") (name "Net-(R2-Pad1)") (class "Default")
      (node (ref "R2") (pin "1") (pinfunction "1_1") (pintype "passive"))
      (node (ref "XP1") (pin "3") (pinfunction "3_3") (pintype "passive"))
    )
    (net (code "72") (name "Net-(R3-Pad1)") (class "Default")
      (node (ref "R3") (pin "1") (pinfunction "1_1") (pintype "passive"))
      (node (ref "XP1") (pin "4") (pinfunction "4_4") (pintype "passive"))
    )
    (net (code "73") (name "Net-(R11-Pad2)") (class "Default")
      (node (ref "R11") (pin "2") (pinfunction "2_2") (pintype "passive"))
      (node (ref "R12") (pin "2") (pinfunction "2_2") (pintype "passive"))
      (node (ref "XP5") (pin "1") (pinfunction "1_1") (pintype "passive"))
    )
    (net (code "74") (name "U_LED") (class "Default")
      (node (ref "C12") (pin "1") (pinfunction "P_1") (pintype "passive"))
      (node (ref "C14") (pin "2") (pinfunction "2_2") (pintype "passive"))
      (node (ref "DA4") (pin "10") (pinfunction "COM_10") (pintype "power_in"))
      (node (ref "DA5") (pin "9") (pinfunction "Vcc_9") (pintype "power_in"))
      (node (ref "DA6") (pin "10") (pinfunction "COM_10") (pintype "power_in"))
      (node (ref "DA7") (pin "9") (pinfunction "Vcc_9") (pintype "power_in"))
      (node (ref "R10") (pin "2") (pinfunction "2_2") (pintype "passive"))
      (node (ref "R12") (pin "1") (pinfunction "1_1") (pintype "passive"))
      (node (ref "XP5") (pin "2") (pinfunction "2_2") (pintype "passive"))
    )
    (net (code "75") (name "unconnected-(DA5-O3-Pad16)") (class "Default")
      (node (ref "DA5") (pin "16") (pinfunction "O3_16") (pintype "open_emitter+no_connect"))
    )
    (net (code "76") (name "unconnected-(DA5-O7-Pad12)") (class "Default")
      (node (ref "DA5") (pin "12") (pinfunction "O7_12") (pintype "open_emitter+no_connect"))
    )
    (net (code "77") (name "unconnected-(DA7-O2-Pad17)") (class "Default")
      (node (ref "DA7") (pin "17") (pinfunction "O2_17") (pintype "open_emitter+no_connect"))
    )
    (net (code "78") (name "unconnected-(DA7-O6-Pad13)") (class "Default")
      (node (ref "DA7") (pin "13") (pinfunction "O6_13") (pintype "open_emitter+no_connect"))
    )
    (net (code "79") (name "unconnected-(DD2-R2IN-Pad8)") (class "Default")
      (node (ref "DD2") (pin "8") (pinfunction "R2IN_8") (pintype "input+no_connect"))
    )
    (net (code "80") (name "unconnected-(DD2-R2OUT-Pad9)") (class "Default")
      (node (ref "DD2") (pin "9") (pinfunction "R2OUT_9") (pintype "output+no_connect"))
    )
    (net (code "81") (name "unconnected-(DD2-T2OUT-Pad7)") (class "Default")
      (node (ref "DD2") (pin "7") (pinfunction "T2OUT_7") (pintype "output+no_connect"))
    )
    (net (code "82") (name "unconnected-(DD3C-PA11-Pad32)") (class "Default")
      (node (ref "DD3") (pin "32") (pinfunction "PA11_32") (pintype "bidirectional"))
    )
    (net (code "83") (name "unconnected-(DD3C-PA12-Pad33)") (class "Default")
      (node (ref "DD3") (pin "33") (pinfunction "PA12_33") (pintype "bidirectional"))
    )
    (net (code "84") (name "unconnected-(DD3C-PA15-Pad38)") (class "Default")
      (node (ref "DD3") (pin "38") (pinfunction "PA15_38") (pintype "bidirectional"))
    )
    (net (code "85") (name "unconnected-(DD3C-PC13{slash}TAMPER-RTC-Pad2)") (class "Default")
      (node (ref "DD3") (pin "2") (pinfunction "PC13/TAMPER-RTC_2") (pintype "bidirectional"))
    )
    (net (code "86") (name "unconnected-(DD3C-PC14{slash}OSC32_IN-Pad3)") (class "Default")
      (node (ref "DD3") (pin "3") (pinfunction "PC14/OSC32_IN_3") (pintype "bidirectional"))
    )
    (net (code "87") (name "unconnected-(DD3C-PC15{slash}OSC32_OUT-Pad4)") (class "Default")
      (node (ref "DD3") (pin "4") (pinfunction "PC15/OSC32_OUT_4") (pintype "bidirectional"))
    )
  )
)
